# schematic.net
KiCad netlist of a schematic drawn in EAGLE
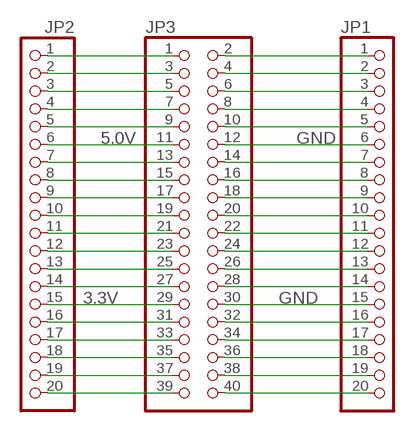
[diagram p0: schematic, sheet 1]

(export (version "E")
  (design (tool "Eeschema 10.0.6"))
  (components
    (comp (ref "JP1")
      (value "PINHD-1X20")
      (footprint "eagle-import:1X20")
      (libsource (lib "eagle-import") (part "PINHD-1X20"))
    )
    (comp (ref "JP2")
      (value "PINHD-1X20")
      (footprint "eagle-import:1X20")
      (libsource (lib "eagle-import") (part "PINHD-1X20"))
    )
    (comp (ref "JP3")
      (value "PINHD-2X20")
      (footprint "eagle-import:2X20")
      (libsource (lib "eagle-import") (part "PINHD-2X20"))
    )
  )
  (nets
    (net (code "1") (name "/3.3V") (class "Default")
      (node (ref "JP2") (pin "15") (pinfunction "15_15") (pintype "passive"))
      (node (ref "JP3") (pin "29") (pinfunction "29_29") (pintype "passive"))
    )
    (net (code "2") (name "/5.0V") (class "Default")
      (node (ref "JP2") (pin "6") (pinfunction "6_6") (pintype "passive"))
      (node (ref "JP3") (pin "11") (pinfunction "11_11") (pintype "passive"))
    )
    (net (code "3") (name "/GND") (class "Default")
      (node (ref "JP1") (pin "15") (pinfunction "15_15") (pintype "passive"))
      (node (ref "JP1") (pin "6") (pinfunction "6_6") (pintype "passive"))
      (node (ref "JP3") (pin "12") (pinfunction "12_12") (pintype "passive"))
      (node (ref "JP3") (pin "30") (pinfunction "30_30") (pintype "passive"))
    )
    (net (code "4") (name "Net-(JP1-Pad1)") (class "Default")
      (node (ref "JP1") (pin "1") (pinfunction "1_1") (pintype "passive"))
      (node (ref "JP3") (pin "2") (pinfunction "2_2") (pintype "passive"))
    )
    (net (code "5") (name "Net-(JP1-Pad2)") (class "Default")
      (node (ref "JP1") (pin "2") (pinfunction "2_2") (pintype "passive"))
      (node (ref "JP3") (pin "4") (pinfunction "4_4") (pintype "passive"))
    )
    (net (code "6") (name "Net-(JP1-Pad3)") (class "Default")
      (node (ref "JP1") (pin "3") (pinfunction "3_3") (pintype "passive"))
      (node (ref "JP3") (pin "6") (pinfunction "6_6") (pintype "passive"))
    )
    (net (code "7") (name "Net-(JP1-Pad4)") (class "Default")
      (node (ref "JP1") (pin "4") (pinfunction "4_4") (pintype "passive"))
      (node (ref "JP3") (pin "8") (pinfunction "8_8") (pintype "passive"))
    )
    (net (code "8") (name "Net-(JP1-Pad5)") (class "Default")
      (node (ref "JP1") (pin "5") (pinfunction "5_5") (pintype "passive"))
      (node (ref "JP3") (pin "10") (pinfunction "10_10") (pintype "passive"))
    )
    (net (code "9") (name "Net-(JP1-Pad7)") (class "Default")
      (node (ref "JP1") (pin "7") (pinfunction "7_7") (pintype "passive"))
      (node (ref "JP3") (pin "14") (pinfunction "14_14") (pintype "passive"))
    )
    (net (code "10") (name "Net-(JP1-Pad8)") (class "Default")
      (node (ref "JP1") (pin "8") (pinfunction "8_8") (pintype "passive"))
      (node (ref "JP3") (pin "16") (pinfunction "16_16") (pintype "passive"))
    )
    (net (code "11") (name "Net-(JP1-Pad9)") (class "Default")
      (node (ref "JP1") (pin "9") (pinfunction "9_9") (pintype "passive"))
      (node (ref "JP3") (pin "18") (pinfunction "18_18") (pintype "passive"))
    )
    (net (code "12") (name "Net-(JP1-Pad10)") (class "Default")
      (node (ref "JP1") (pin "10") (pinfunction "10_10") (pintype "passive"))
      (node (ref "JP3") (pin "20") (pinfunction "20_20") (pintype "passive"))
    )
    (net (code "13") (name "Net-(JP1-Pad11)") (class "Default")
      (node (ref "JP1") (pin "11") (pinfunction "11_11") (pintype "passive"))
      (node (ref "JP3") (pin "22") (pinfunction "22_22") (pintype "passive"))
    )
    (net (code "14") (name "Net-(JP1-Pad12)") (class "Default")
      (node (ref "JP1") (pin "12") (pinfunction "12_12") (pintype "passive"))
      (node (ref "JP3") (pin "24") (pinfunction "24_24") (pintype "passive"))
    )
    (net (code "15") (name "Net-(JP1-Pad13)") (class "Default")
      (node (ref "JP1") (pin "13") (pinfunction "13_13") (pintype "passive"))
      (node (ref "JP3") (pin "26") (pinfunction "26_26") (pintype "passive"))
    )
    (net (code "16") (name "Net-(JP1-Pad14)") (class "Default")
      (node (ref "JP1") (pin "14") (pinfunction "14_14") (pintype "passive"))
      (node (ref "JP3") (pin "28") (pinfunction "28_28") (pintype "passive"))
    )
    (net (code "17") (name "Net-(JP1-Pad16)") (class "Default")
      (node (ref "JP1") (pin "16") (pinfunction "16_16") (pintype "passive"))
      (node (ref "JP3") (pin "32") (pinfunction "32_32") (pintype "passive"))
    )
    (net (code "18") (name "Net-(JP1-Pad17)") (class "Default")
      (node (ref "JP1") (pin "17") (pinfunction "17_17") (pintype "passive"))
      (node (ref "JP3") (pin "34") (pinfunction "34_34") (pintype "passive"))
    )
    (net (code "19") (name "Net-(JP1-Pad18)") (class "Default")
      (node (ref "JP1") (pin "18") (pinfunction "18_18") (pintype "passive"))
      (node (ref "JP3") (pin "36") (pinfunction "36_36") (pintype "passive"))
    )
    (net (code "20") (name "Net-(JP1-Pad19)") (class "Default")
      (node (ref "JP1") (pin "19") (pinfunction "19_19") (pintype "passive"))
      (node (ref "JP3") (pin "38") (pinfunction "38_38") (pintype "passive"))
    )
    (net (code "21") (name "Net-(JP1-Pad20)") (class "Default")
      (node (ref "JP1") (pin "20") (pinfunction "20_20") (pintype "passive"))
      (node (ref "JP3") (pin "40") (pinfunction "40_40") (pintype "passive"))
    )
    (net (code "22") (name "Net-(JP2-Pad1)") (class "Default")
      (node (ref "JP2") (pin "1") (pinfunction "1_1") (pintype "passive"))
      (node (ref "JP3") (pin "1") (pinfunction "1_1") (pintype "passive"))
    )
    (net (code "23") (name "Net-(JP2-Pad2)") (class "Default")
      (node (ref "JP2") (pin "2") (pinfunction "2_2") (pintype "passive"))
      (node (ref "JP3") (pin "3") (pinfunction "3_3") (pintype "passive"))
    )
    (net (code "24") (name "Net-(JP2-Pad3)") (class "Default")
      (node (ref "JP2") (pin "3") (pinfunction "3_3") (pintype "passive"))
      (node (ref "JP3") (pin "5") (pinfunction "5_5") (pintype "passive"))
    )
    (net (code "25") (name "Net-(JP2-Pad4)") (class "Default")
      (node (ref "JP2") (pin "4") (pinfunction "4_4") (pintype "passive"))
      (node (ref "JP3") (pin "7") (pinfunction "7_7") (pintype "passive"))
    )
    (net (code "26") (name "Net-(JP2-Pad5)") (class "Default")
      (node (ref "JP2") (pin "5") (pinfunction "5_5") (pintype "passive"))
      (node (ref "JP3") (pin "9") (pinfunction "9_9") (pintype "passive"))
    )
    (net (code "27") (name "Net-(JP2-Pad7)") (class "Default")
      (node (ref "JP2") (pin "7") (pinfunction "7_7") (pintype "passive"))
      (node (ref "JP3") (pin "13") (pinfunction "13_13") (pintype "passive"))
    )
    (net (code "28") (name "Net-(JP2-Pad8)") (class "Default")
      (node (ref "JP2") (pin "8") (pinfunction "8_8") (pintype "passive"))
      (node (ref "JP3") (pin "15") (pinfunction "15_15") (pintype "passive"))
    )
    (net (code "29") (name "Net-(JP2-Pad9)") (class "Default")
      (node (ref "JP2") (pin "9") (pinfunction "9_9") (pintype "passive"))
      (node (ref "JP3") (pin "17") (pinfunction "17_17") (pintype "passive"))
    )
    (net (code "30") (name "Net-(JP2-Pad10)") (class "Default")
      (node (ref "JP2") (pin "10") (pinfunction "10_10") (pintype "passive"))
      (node (ref "JP3") (pin "19") (pinfunction "19_19") (pintype "passive"))
    )
    (net (code "31") (name "Net-(JP2-Pad11)") (class "Default")
      (node (ref "JP2") (pin "11") (pinfunction "11_11") (pintype "passive"))
      (node (ref "JP3") (pin "21") (pinfunction "21_21") (pintype "passive"))
    )
    (net (code "32") (name "Net-(JP2-Pad12)") (class "Default")
      (node (ref "JP2") (pin "12") (pinfunction "12_12") (pintype "passive"))
      (node (ref "JP3") (pin "23") (pinfunction "23_23") (pintype "passive"))
    )
    (net (code "33") (name "Net-(JP2-Pad13)") (class "Default")
      (node (ref "JP2") (pin "13") (pinfunction "13_13") (pintype "passive"))
      (node (ref "JP3") (pin "25") (pinfunction "25_25") (pintype "passive"))
    )
    (net (code "34") (name "Net-(JP2-Pad14)") (class "Default")
      (node (ref "JP2") (pin "14") (pinfunction "14_14") (pintype "passive"))
      (node (ref "JP3") (pin "27") (pinfunction "27_27") (pintype "passive"))
    )
    (net (code "35") (name "Net-(JP2-Pad16)") (class "Default")
      (node (ref "JP2") (pin "16") (pinfunction "16_16") (pintype "passive"))
      (node (ref "JP3") (pin "31") (pinfunction "31_31") (pintype "passive"))
    )
    (net (code "36") (name "Net-(JP2-Pad17)") (class "Default")
      (node (ref "JP2") (pin "17") (pinfunction "17_17") (pintype "passive"))
      (node (ref "JP3") (pin "33") (pinfunction "33_33") (pintype "passive"))
    )
    (net (code "37") (name "Net-(JP2-Pad18)") (class "Default")
      (node (ref "JP2") (pin "18") (pinfunction "18_18") (pintype "passive"))
      (node (ref "JP3") (pin "35") (pinfunction "35_35") (pintype "passive"))
    )
    (net (code "38") (name "Net-(JP2-Pad19)") (class "Default")
      (node (ref "JP2") (pin "19") (pinfunction "19_19") (pintype "passive"))
      (node (ref "JP3") (pin "37") (pinfunction "37_37") (pintype "passive"))
    )
    (net (code "39") (name "Net-(JP2-Pad20)") (class "Default")
      (node (ref "JP2") (pin "20") (pinfunction "20_20") (pintype "passive"))
      (node (ref "JP3") (pin "39") (pinfunction "39_39") (pintype "passive"))
    )
  )
)
